# EtherCAT.net
KiCad netlist of a schematic drawn in Altium Designer
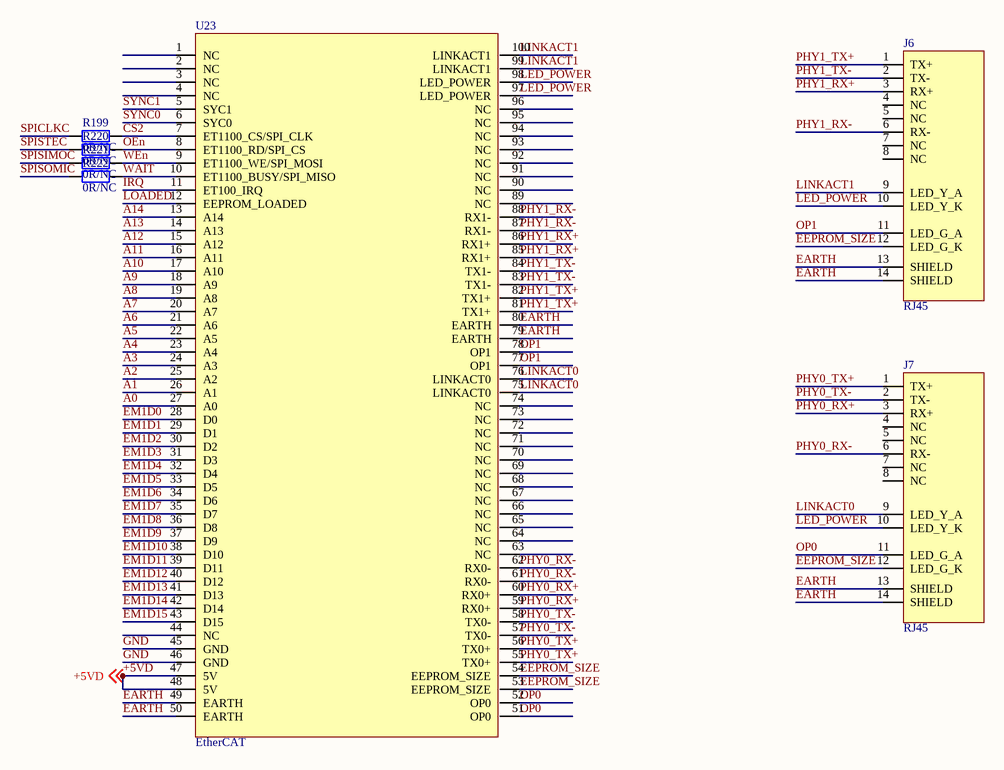
[diagram p0: EtherCAT.SchDoc]

(export (version "E")
  (design (tool "Eeschema 10.0.6"))
  (components
    (comp (ref "J6") (value "RJ45") (footprint "RJ45") (libsource (lib "Main_C") (part "RJ45")))
    (comp (ref "J7") (value "RJ45") (footprint "RJ45") (libsource (lib "Main_C") (part "RJ45")))
    (comp (ref "R199")
      (value "0R/NC")
      (footprint "0603R")
      (description "Resistor")
      (fields (field (name "PUBLISHER") "Altium Limited"))
      (libsource (lib "Main_C") (part "Res2"))
    )
    (comp (ref "R220")
      (value "0R/NC")
      (footprint "0603R")
      (description "Resistor")
      (fields (field (name "PUBLISHER") "Altium Limited"))
      (libsource (lib "Main_C") (part "Res2"))
    )
    (comp (ref "R221")
      (value "0R/NC")
      (footprint "0603R")
      (description "Resistor")
      (fields (field (name "PUBLISHER") "Altium Limited"))
      (libsource (lib "Main_C") (part "Res2"))
    )
    (comp (ref "R222")
      (value "0R/NC")
      (footprint "0603R")
      (description "Resistor")
      (fields (field (name "PUBLISHER") "Altium Limited"))
      (libsource (lib "Main_C") (part "Res2"))
    )
    (comp (ref "U23")
      (value "EtherCAT")
      (footprint "EtherCAT")
      (libsource (lib "Main_C") (part "EtherCAT_MOD"))
    )
  )
  (nets
    (net (code "1") (name "+5VD") (class "Default")
      (node (ref "U23") (pin "47") (pinfunction "5V_47") (pintype "passive"))
      (node (ref "U23") (pin "48") (pinfunction "5V_48") (pintype "passive"))
    )
    (net (code "2") (name "/A0") (class "Default")
      (node (ref "U23") (pin "27") (pinfunction "A0_27") (pintype "passive"))
    )
    (net (code "3") (name "/A1") (class "Default")
      (node (ref "U23") (pin "26") (pinfunction "A1_26") (pintype "passive"))
    )
    (net (code "4") (name "/A2") (class "Default")
      (node (ref "U23") (pin "25") (pinfunction "A2_25") (pintype "passive"))
    )
    (net (code "5") (name "/A3") (class "Default")
      (node (ref "U23") (pin "24") (pinfunction "A3_24") (pintype "passive"))
    )
    (net (code "6") (name "/A4") (class "Default")
      (node (ref "U23") (pin "23") (pinfunction "A4_23") (pintype "passive"))
    )
    (net (code "7") (name "/A5") (class "Default")
      (node (ref "U23") (pin "22") (pinfunction "A5_22") (pintype "passive"))
    )
    (net (code "8") (name "/A6") (class "Default")
      (node (ref "U23") (pin "21") (pinfunction "A6_21") (pintype "passive"))
    )
    (net (code "9") (name "/A7") (class "Default")
      (node (ref "U23") (pin "20") (pinfunction "A7_20") (pintype "passive"))
    )
    (net (code "10") (name "/A8") (class "Default")
      (node (ref "U23") (pin "19") (pinfunction "A8_19") (pintype "passive"))
    )
    (net (code "11") (name "/A9") (class "Default")
      (node (ref "U23") (pin "18") (pinfunction "A9_18") (pintype "passive"))
    )
    (net (code "12") (name "/A10") (class "Default")
      (node (ref "U23") (pin "17") (pinfunction "A10_17") (pintype "passive"))
    )
    (net (code "13") (name "/A11") (class "Default")
      (node (ref "U23") (pin "16") (pinfunction "A11_16") (pintype "passive"))
    )
    (net (code "14") (name "/A12") (class "Default")
      (node (ref "U23") (pin "15") (pinfunction "A12_15") (pintype "passive"))
    )
    (net (code "15") (name "/A13") (class "Default")
      (node (ref "U23") (pin "14") (pinfunction "A13_14") (pintype "passive"))
    )
    (net (code "16") (name "/A14") (class "Default")
      (node (ref "U23") (pin "13") (pinfunction "A14_13") (pintype "passive"))
    )
    (net (code "17") (name "/CS2") (class "Default")
      (node (ref "R199") (pin "1") (pinfunction "1_1") (pintype "passive"))
      (node (ref "U23") (pin "7") (pinfunction "ET1100_CS/SPI_CLK_7") (pintype "passive"))
    )
    (net (code "18") (name "/EARTH") (class "Default")
      (node (ref "J6") (pin "13") (pinfunction "SHIELD_13") (pintype "passive"))
      (node (ref "J6") (pin "14") (pinfunction "SHIELD_14") (pintype "passive"))
      (node (ref "J7") (pin "13") (pinfunction "SHIELD_13") (pintype "passive"))
      (node (ref "J7") (pin "14") (pinfunction "SHIELD_14") (pintype "passive"))
      (node (ref "U23") (pin "49") (pinfunction "EARTH_49") (pintype "passive"))
      (node (ref "U23") (pin "50") (pinfunction "EARTH_50") (pintype "passive"))
      (node (ref "U23") (pin "79") (pinfunction "EARTH_79") (pintype "passive"))
      (node (ref "U23") (pin "80") (pinfunction "EARTH_80") (pintype "passive"))
    )
    (net (code "19") (name "/EEPROM_SIZE") (class "Default")
      (node (ref "J6") (pin "12") (pinfunction "LED_G_K_12") (pintype "passive"))
      (node (ref "J7") (pin "12") (pinfunction "LED_G_K_12") (pintype "passive"))
      (node (ref "U23") (pin "53") (pinfunction "EEPROM_SIZE_53") (pintype "passive"))
      (node (ref "U23") (pin "54") (pinfunction "EEPROM_SIZE_54") (pintype "passive"))
    )
    (net (code "20") (name "/EM1D0") (class "Default")
      (node (ref "U23") (pin "28") (pinfunction "D0_28") (pintype "passive"))
    )
    (net (code "21") (name "/EM1D1") (class "Default")
      (node (ref "U23") (pin "29") (pinfunction "D1_29") (pintype "passive"))
    )
    (net (code "22") (name "/EM1D2") (class "Default")
      (node (ref "U23") (pin "30") (pinfunction "D2_30") (pintype "passive"))
    )
    (net (code "23") (name "/EM1D3") (class "Default")
      (node (ref "U23") (pin "31") (pinfunction "D3_31") (pintype "passive"))
    )
    (net (code "24") (name "/EM1D4") (class "Default")
      (node (ref "U23") (pin "32") (pinfunction "D4_32") (pintype "passive"))
    )
    (net (code "25") (name "/EM1D5") (class "Default")
      (node (ref "U23") (pin "33") (pinfunction "D5_33") (pintype "passive"))
    )
    (net (code "26") (name "/EM1D6") (class "Default")
      (node (ref "U23") (pin "34") (pinfunction "D6_34") (pintype "passive"))
    )
    (net (code "27") (name "/EM1D7") (class "Default")
      (node (ref "U23") (pin "35") (pinfunction "D7_35") (pintype "passive"))
    )
    (net (code "28") (name "/EM1D8") (class "Default")
      (node (ref "U23") (pin "36") (pinfunction "D8_36") (pintype "passive"))
    )
    (net (code "29") (name "/EM1D9") (class "Default")
      (node (ref "U23") (pin "37") (pinfunction "D9_37") (pintype "passive"))
    )
    (net (code "30") (name "/EM1D10") (class "Default")
      (node (ref "U23") (pin "38") (pinfunction "D10_38") (pintype "passive"))
    )
    (net (code "31") (name "/EM1D11") (class "Default")
      (node (ref "U23") (pin "39") (pinfunction "D11_39") (pintype "passive"))
    )
    (net (code "32") (name "/EM1D12") (class "Default")
      (node (ref "U23") (pin "40") (pinfunction "D12_40") (pintype "passive"))
    )
    (net (code "33") (name "/EM1D13") (class "Default")
      (node (ref "U23") (pin "41") (pinfunction "D13_41") (pintype "passive"))
    )
    (net (code "34") (name "/EM1D14") (class "Default")
      (node (ref "U23") (pin "42") (pinfunction "D14_42") (pintype "passive"))
    )
    (net (code "35") (name "/EM1D15") (class "Default")
      (node (ref "U23") (pin "43") (pinfunction "D15_43") (pintype "passive"))
    )
    (net (code "36") (name "/GND") (class "Default")
      (node (ref "U23") (pin "45") (pinfunction "GND_45") (pintype "passive"))
      (node (ref "U23") (pin "46") (pinfunction "GND_46") (pintype "passive"))
    )
    (net (code "37") (name "/IRQ") (class "Default")
      (node (ref "U23") (pin "11") (pinfunction "ET100_IRQ_11") (pintype "passive"))
    )
    (net (code "38") (name "/LED_POWER") (class "Default")
      (node (ref "J6") (pin "10") (pinfunction "LED_Y_K_10") (pintype "passive"))
      (node (ref "J7") (pin "10") (pinfunction "LED_Y_K_10") (pintype "passive"))
      (node (ref "U23") (pin "97") (pinfunction "LED_POWER_97") (pintype "passive"))
      (node (ref "U23") (pin "98") (pinfunction "LED_POWER_98") (pintype "passive"))
    )
    (net (code "39") (name "/LINKACT0") (class "Default")
      (node (ref "J7") (pin "9") (pinfunction "LED_Y_A_9") (pintype "passive"))
      (node (ref "U23") (pin "75") (pinfunction "LINKACT0_75") (pintype "passive"))
      (node (ref "U23") (pin "76") (pinfunction "LINKACT0_76") (pintype "passive"))
    )
    (net (code "40") (name "/LINKACT1") (class "Default")
      (node (ref "J6") (pin "9") (pinfunction "LED_Y_A_9") (pintype "passive"))
      (node (ref "U23") (pin "100") (pinfunction "LINKACT1_100") (pintype "passive"))
      (node (ref "U23") (pin "99") (pinfunction "LINKACT1_99") (pintype "passive"))
    )
    (net (code "41") (name "/LOADED") (class "Default")
      (node (ref "U23") (pin "12") (pinfunction "EEPROM_LOADED_12") (pintype "passive"))
    )
    (net (code "42") (name "/OEn") (class "Default")
      (node (ref "R220") (pin "1") (pinfunction "1_1") (pintype "passive"))
      (node (ref "U23") (pin "8") (pinfunction "ET1100_RD/SPI_CS_8") (pintype "passive"))
    )
    (net (code "43") (name "/OP0") (class "Default")
      (node (ref "J7") (pin "11") (pinfunction "LED_G_A_11") (pintype "passive"))
      (node (ref "U23") (pin "51") (pinfunction "OP0_51") (pintype "passive"))
      (node (ref "U23") (pin "52") (pinfunction "OP0_52") (pintype "passive"))
    )
    (net (code "44") (name "/OP1") (class "Default")
      (node (ref "J6") (pin "11") (pinfunction "LED_G_A_11") (pintype "passive"))
      (node (ref "U23") (pin "77") (pinfunction "OP1_77") (pintype "passive"))
      (node (ref "U23") (pin "78") (pinfunction "OP1_78") (pintype "passive"))
    )
    (net (code "45") (name "/PHY0_RX+") (class "Default")
      (node (ref "J7") (pin "3") (pinfunction "RX+_3") (pintype "passive"))
      (node (ref "U23") (pin "59") (pinfunction "RX0+_59") (pintype "passive"))
      (node (ref "U23") (pin "60") (pinfunction "RX0+_60") (pintype "passive"))
    )
    (net (code "46") (name "/PHY0_RX-") (class "Default")
      (node (ref "J7") (pin "6") (pinfunction "RX-_6") (pintype "passive"))
      (node (ref "U23") (pin "61") (pinfunction "RX0-_61") (pintype "passive"))
      (node (ref "U23") (pin "62") (pinfunction "RX0-_62") (pintype "passive"))
    )
    (net (code "47") (name "/PHY0_TX+") (class "Default")
      (node (ref "J7") (pin "1") (pinfunction "TX+_1") (pintype "passive"))
      (node (ref "U23") (pin "55") (pinfunction "TX0+_55") (pintype "passive"))
      (node (ref "U23") (pin "56") (pinfunction "TX0+_56") (pintype "passive"))
    )
    (net (code "48") (name "/PHY0_TX-") (class "Default")
      (node (ref "J7") (pin "2") (pinfunction "TX-_2") (pintype "passive"))
      (node (ref "U23") (pin "57") (pinfunction "TX0-_57") (pintype "passive"))
      (node (ref "U23") (pin "58") (pinfunction "TX0-_58") (pintype "passive"))
    )
    (net (code "49") (name "/PHY1_RX+") (class "Default")
      (node (ref "J6") (pin "3") (pinfunction "RX+_3") (pintype "passive"))
      (node (ref "U23") (pin "85") (pinfunction "RX1+_85") (pintype "passive"))
      (node (ref "U23") (pin "86") (pinfunction "RX1+_86") (pintype "passive"))
    )
    (net (code "50") (name "/PHY1_RX-") (class "Default")
      (node (ref "J6") (pin "6") (pinfunction "RX-_6") (pintype "passive"))
      (node (ref "U23") (pin "87") (pinfunction "RX1-_87") (pintype "passive"))
      (node (ref "U23") (pin "88") (pinfunction "RX1-_88") (pintype "passive"))
    )
    (net (code "51") (name "/PHY1_TX+") (class "Default")
      (node (ref "J6") (pin "1") (pinfunction "TX+_1") (pintype "passive"))
      (node (ref "U23") (pin "81") (pinfunction "TX1+_81") (pintype "passive"))
      (node (ref "U23") (pin "82") (pinfunction "TX1+_82") (pintype "passive"))
    )
    (net (code "52") (name "/PHY1_TX-") (class "Default")
      (node (ref "J6") (pin "2") (pinfunction "TX-_2") (pintype "passive"))
      (node (ref "U23") (pin "83") (pinfunction "TX1-_83") (pintype "passive"))
      (node (ref "U23") (pin "84") (pinfunction "TX1-_84") (pintype "passive"))
    )
    (net (code "53") (name "/SPICLKC") (class "Default")
      (node (ref "R199") (pin "2") (pinfunction "2_2") (pintype "passive"))
    )
    (net (code "54") (name "/SPISIMOC") (class "Default")
      (node (ref "R221") (pin "2") (pinfunction "2_2") (pintype "passive"))
    )
    (net (code "55") (name "/SPISOMIC") (class "Default")
      (node (ref "R222") (pin "2") (pinfunction "2_2") (pintype "passive"))
    )
    (net (code "56") (name "/SPISTEC") (class "Default")
      (node (ref "R220") (pin "2") (pinfunction "2_2") (pintype "passive"))
    )
    (net (code "57") (name "/SYNC0") (class "Default")
      (node (ref "U23") (pin "6") (pinfunction "SYC0_6") (pintype "passive"))
    )
    (net (code "58") (name "/SYNC1") (class "Default")
      (node (ref "U23") (pin "5") (pinfunction "SYC1_5") (pintype "passive"))
    )
    (net (code "59") (name "/WAIT") (class "Default")
      (node (ref "R222") (pin "1") (pinfunction "1_1") (pintype "passive"))
      (node (ref "U23") (pin "10") (pinfunction "ET1100_BUSY/SPI_MISO_10") (pintype "passive"))
    )
    (net (code "60") (name "/WEn") (class "Default")
      (node (ref "R221") (pin "1") (pinfunction "1_1") (pintype "passive"))
      (node (ref "U23") (pin "9") (pinfunction "ET1100_WE/SPI_MOSI_9") (pintype "passive"))
    )
    (net (code "61") (name "unconnected-(J6-NC-Pad4)") (class "Default")
      (node (ref "J6") (pin "4") (pinfunction "NC_4") (pintype "passive"))
    )
    (net (code "62") (name "unconnected-(J6-NC-Pad5)") (class "Default")
      (node (ref "J6") (pin "5") (pinfunction "NC_5") (pintype "passive"))
    )
    (net (code "63") (name "unconnected-(J6-NC-Pad7)") (class "Default")
      (node (ref "J6") (pin "7") (pinfunction "NC_7") (pintype "passive"))
    )
    (net (code "64") (name "unconnected-(J6-NC-Pad8)") (class "Default")
      (node (ref "J6") (pin "8") (pinfunction "NC_8") (pintype "passive"))
    )
    (net (code "65") (name "unconnected-(J7-NC-Pad4)") (class "Default")
      (node (ref "J7") (pin "4") (pinfunction "NC_4") (pintype "passive"))
    )
    (net (code "66") (name "unconnected-(J7-NC-Pad5)") (class "Default")
      (node (ref "J7") (pin "5") (pinfunction "NC_5") (pintype "passive"))
    )
    (net (code "67") (name "unconnected-(J7-NC-Pad7)") (class "Default")
      (node (ref "J7") (pin "7") (pinfunction "NC_7") (pintype "passive"))
    )
    (net (code "68") (name "unconnected-(J7-NC-Pad8)") (class "Default")
      (node (ref "J7") (pin "8") (pinfunction "NC_8") (pintype "passive"))
    )
    (net (code "69") (name "unconnected-(U23-NC-Pad1)") (class "Default")
      (node (ref "U23") (pin "1") (pinfunction "NC_1") (pintype "passive"))
    )
    (net (code "70") (name "unconnected-(U23-NC-Pad2)") (class "Default")
      (node (ref "U23") (pin "2") (pinfunction "NC_2") (pintype "passive"))
    )
    (net (code "71") (name "unconnected-(U23-NC-Pad3)") (class "Default")
      (node (ref "U23") (pin "3") (pinfunction "NC_3") (pintype "passive"))
    )
    (net (code "72") (name "unconnected-(U23-NC-Pad4)") (class "Default")
      (node (ref "U23") (pin "4") (pinfunction "NC_4") (pintype "passive"))
    )
    (net (code "73") (name "unconnected-(U23-NC-Pad44)") (class "Default")
      (node (ref "U23") (pin "44") (pinfunction "NC_44") (pintype "passive"))
    )
    (net (code "74") (name "unconnected-(U23-NC-Pad63)") (class "Default")
      (node (ref "U23") (pin "63") (pinfunction "NC_63") (pintype "passive"))
    )
    (net (code "75") (name "unconnected-(U23-NC-Pad64)") (class "Default")
      (node (ref "U23") (pin "64") (pinfunction "NC_64") (pintype "passive"))
    )
    (net (code "76") (name "unconnected-(U23-NC-Pad65)") (class "Default")
      (node (ref "U23") (pin "65") (pinfunction "NC_65") (pintype "passive"))
    )
    (net (code "77") (name "unconnected-(U23-NC-Pad66)") (class "Default")
      (node (ref "U23") (pin "66") (pinfunction "NC_66") (pintype "passive"))
    )
    (net (code "78") (name "unconnected-(U23-NC-Pad67)") (class "Default")
      (node (ref "U23") (pin "67") (pinfunction "NC_67") (pintype "passive"))
    )
    (net (code "79") (name "unconnected-(U23-NC-Pad68)") (class "Default")
      (node (ref "U23") (pin "68") (pinfunction "NC_68") (pintype "passive"))
    )
    (net (code "80") (name "unconnected-(U23-NC-Pad69)") (class "Default")
      (node (ref "U23") (pin "69") (pinfunction "NC_69") (pintype "passive"))
    )
    (net (code "81") (name "unconnected-(U23-NC-Pad70)") (class "Default")
      (node (ref "U23") (pin "70") (pinfunction "NC_70") (pintype "passive"))
    )
    (net (code "82") (name "unconnected-(U23-NC-Pad71)") (class "Default")
      (node (ref "U23") (pin "71") (pinfunction "NC_71") (pintype "passive"))
    )
    (net (code "83") (name "unconnected-(U23-NC-Pad72)") (class "Default")
      (node (ref "U23") (pin "72") (pinfunction "NC_72") (pintype "passive"))
    )
    (net (code "84") (name "unconnected-(U23-NC-Pad73)") (class "Default")
      (node (ref "U23") (pin "73") (pinfunction "NC_73") (pintype "passive"))
    )
    (net (code "85") (name "unconnected-(U23-NC-Pad74)") (class "Default")
      (node (ref "U23") (pin "74") (pinfunction "NC_74") (pintype "passive"))
    )
    (net (code "86") (name "unconnected-(U23-NC-Pad89)") (class "Default")
      (node (ref "U23") (pin "89") (pinfunction "NC_89") (pintype "passive"))
    )
    (net (code "87") (name "unconnected-(U23-NC-Pad90)") (class "Default")
      (node (ref "U23") (pin "90") (pinfunction "NC_90") (pintype "passive"))
    )
    (net (code "88") (name "unconnected-(U23-NC-Pad91)") (class "Default")
      (node (ref "U23") (pin "91") (pinfunction "NC_91") (pintype "passive"))
    )
    (net (code "89") (name "unconnected-(U23-NC-Pad92)") (class "Default")
      (node (ref "U23") (pin "92") (pinfunction "NC_92") (pintype "passive"))
    )
    (net (code "90") (name "unconnected-(U23-NC-Pad93)") (class "Default")
      (node (ref "U23") (pin "93") (pinfunction "NC_93") (pintype "passive"))
    )
    (net (code "91") (name "unconnected-(U23-NC-Pad94)") (class "Default")
      (node (ref "U23") (pin "94") (pinfunction "NC_94") (pintype "passive"))
    )
    (net (code "92") (name "unconnected-(U23-NC-Pad95)") (class "Default")
      (node (ref "U23") (pin "95") (pinfunction "NC_95") (pintype "passive"))
    )
    (net (code "93") (name "unconnected-(U23-NC-Pad96)") (class "Default")
      (node (ref "U23") (pin "96") (pinfunction "NC_96") (pintype "passive"))
    )
  )
)
